# RPi-WD-Packet-Interface_-_RJ45.net
KiCad netlist of a schematic drawn in EAGLE
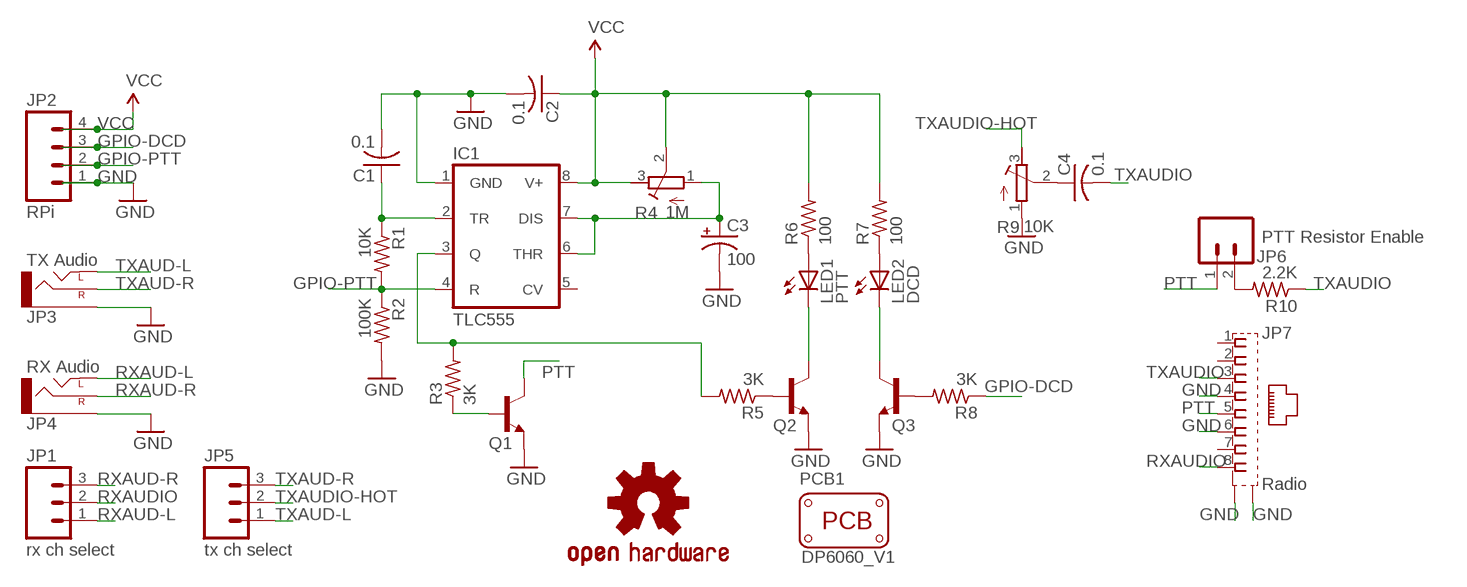
[diagram p0: schematic, sheet 1]

(export (version "E")
  (design (tool "Eeschema 10.0.6"))
  (components
    (comp (ref "C1")
      (value "0.1")
      (footprint "eagle-import:C025-025X050")
      (libsource (lib "eagle-import") (part "C-US025-025X050"))
    )
    (comp (ref "C2")
      (value "0.1")
      (footprint "eagle-import:C025-025X050")
      (libsource (lib "eagle-import") (part "C-US025-025X050"))
    )
    (comp (ref "C3")
      (value "100")
      (footprint "eagle-import:E2-5")
      (libsource (lib "eagle-import") (part "CPOL-USE2-5"))
    )
    (comp (ref "C4")
      (value "0.1")
      (footprint "eagle-import:C025-025X050")
      (libsource (lib "eagle-import") (part "C-US025-025X050"))
    )
    (comp (ref "IC1")
      (value "TLC555")
      (footprint "eagle-import:DIL08")
      (libsource (lib "eagle-import") (part "555NLM"))
    )
    (comp (ref "JP1")
      (value "rx ch select")
      (footprint "eagle-import:1X03")
      (libsource (lib "eagle-import") (part "M03PTH"))
    )
    (comp (ref "JP2")
      (value "RPi")
      (footprint "eagle-import:1X04")
      (libsource (lib "eagle-import") (part "M04PTH"))
    )
    (comp (ref "JP3")
      (value "TX Audio")
      (footprint "eagle-import:AUDIO-JACK")
      (libsource (lib "eagle-import") (part "AUDIO-JACKPTH"))
    )
    (comp (ref "JP4")
      (value "RX Audio")
      (footprint "eagle-import:AUDIO-JACK")
      (libsource (lib "eagle-import") (part "AUDIO-JACKPTH"))
    )
    (comp (ref "JP5")
      (value "tx ch select")
      (footprint "eagle-import:1X03")
      (libsource (lib "eagle-import") (part "M03PTH"))
    )
    (comp (ref "JP6")
      (value "PTT Resistor Enable")
      (footprint "eagle-import:1X02")
      (libsource (lib "eagle-import") (part "M02PTH"))
    )
    (comp (ref "JP7")
      (value "Radio")
      (footprint "eagle-import:0446200002")
      (fields (field (name "MF") "MOLEX") (field (name "MPN") "0446200002"))
      (libsource (lib "eagle-import") (part "0446200002"))
    )
    (comp (ref "LED1")
      (value "PTT")
      (footprint "eagle-import:LED5MM")
      (libsource (lib "eagle-import") (part "LED5MM"))
    )
    (comp (ref "LED2")
      (value "DCD")
      (footprint "eagle-import:LED5MM")
      (libsource (lib "eagle-import") (part "LED5MM"))
    )
    (comp (ref "LOGO1")
      (value "OSHW-LOGOM")
      (footprint "eagle-import:OSHW-LOGO-M")
      (libsource (lib "eagle-import") (part "OSHW-LOGOM"))
    )
    (comp (ref "PCB1")
      (value "PCB_DP_SQUARE-6X6")
      (footprint "eagle-import:DP6060_V1")
      (libsource (lib "eagle-import") (part "PCB_DP_SQUARE-6X6"))
    )
    (comp (ref "Q1")
      (value "PTT")
      (footprint "eagle-import:TO-92-AMMO")
      (libsource (lib "eagle-import") (part "TRANSISTOR_NPNTO-92-AMMO"))
    )
    (comp (ref "Q2")
      (value "PTT-LED")
      (footprint "eagle-import:TO-92-AMMO")
      (libsource (lib "eagle-import") (part "TRANSISTOR_NPNTO-92-AMMO"))
    )
    (comp (ref "Q3")
      (value "DCD-LED")
      (footprint "eagle-import:TO-92-AMMO")
      (libsource (lib "eagle-import") (part "TRANSISTOR_NPNTO-92-AMMO"))
    )
    (comp (ref "R1")
      (value "10K")
      (footprint "eagle-import:0207_7")
      (libsource (lib "eagle-import") (part "R-US_0207/7"))
    )
    (comp (ref "R2")
      (value "100K")
      (footprint "eagle-import:0207_7")
      (libsource (lib "eagle-import") (part "R-US_0207/7"))
    )
    (comp (ref "R3")
      (value "3K")
      (footprint "eagle-import:0207_7")
      (libsource (lib "eagle-import") (part "R-US_0207/7"))
    )
    (comp (ref "R4")
      (value "1M")
      (footprint "eagle-import:RTRIM3296W")
      (libsource (lib "eagle-import") (part "R-TRIMM3296W"))
    )
    (comp (ref "R5")
      (value "3K")
      (footprint "eagle-import:0207_7")
      (libsource (lib "eagle-import") (part "R-US_0207/7"))
    )
    (comp (ref "R6")
      (value "100")
      (footprint "eagle-import:0207_7")
      (libsource (lib "eagle-import") (part "R-US_0207/7"))
    )
    (comp (ref "R7")
      (value "100")
      (footprint "eagle-import:0207_7")
      (libsource (lib "eagle-import") (part "R-US_0207/7"))
    )
    (comp (ref "R8")
      (value "3K")
      (footprint "eagle-import:0207_7")
      (libsource (lib "eagle-import") (part "R-US_0207/7"))
    )
    (comp (ref "R9")
      (value "10K")
      (footprint "eagle-import:RTRIM3362P")
      (libsource (lib "eagle-import") (part "RTRIM-3362P"))
    )
    (comp (ref "R10")
      (value "2.2K")
      (footprint "eagle-import:0207_7")
      (libsource (lib "eagle-import") (part "R-US_0207/7"))
    )
  )
  (nets
    (net (code "1") (name "/GPIO-DCD") (class "Default")
      (node (ref "JP2") (pin "3") (pinfunction "3_3") (pintype "passive"))
      (node (ref "R8") (pin "1") (pinfunction "1_1") (pintype "passive"))
    )
    (net (code "2") (name "/GPIO-PTT") (class "Default")
      (node (ref "IC1") (pin "4") (pinfunction "R_4") (pintype "input"))
      (node (ref "JP2") (pin "2") (pinfunction "2_2") (pintype "passive"))
      (node (ref "R1") (pin "2") (pinfunction "2_2") (pintype "passive"))
      (node (ref "R2") (pin "1") (pinfunction "1_1") (pintype "passive"))
    )
    (net (code "3") (name "/PTT") (class "Default")
      (node (ref "JP6") (pin "1") (pinfunction "1_1") (pintype "passive"))
      (node (ref "JP7") (pin "5") (pinfunction "5_5") (pintype "passive"))
      (node (ref "Q1") (pin "3") (pinfunction "C_3") (pintype "passive"))
    )
    (net (code "4") (name "/RXAUD-L") (class "Default")
      (node (ref "JP1") (pin "1") (pinfunction "1_1") (pintype "passive"))
      (node (ref "JP4") (pin "TIP") (pinfunction "LEFT_TIP") (pintype "bidirectional"))
    )
    (net (code "5") (name "/RXAUD-R") (class "Default")
      (node (ref "JP1") (pin "3") (pinfunction "3_3") (pintype "passive"))
      (node (ref "JP4") (pin "RING") (pinfunction "RIGHT_RING") (pintype "bidirectional"))
    )
    (net (code "6") (name "/RXAUDIO") (class "Default")
      (node (ref "JP1") (pin "2") (pinfunction "2_2") (pintype "passive"))
      (node (ref "JP7") (pin "8") (pinfunction "8_8") (pintype "passive"))
    )
    (net (code "7") (name "/TXAUD-L") (class "Default")
      (node (ref "JP3") (pin "TIP") (pinfunction "LEFT_TIP") (pintype "bidirectional"))
      (node (ref "JP5") (pin "1") (pinfunction "1_1") (pintype "passive"))
    )
    (net (code "8") (name "/TXAUD-R") (class "Default")
      (node (ref "JP3") (pin "RING") (pinfunction "RIGHT_RING") (pintype "bidirectional"))
      (node (ref "JP5") (pin "3") (pinfunction "3_3") (pintype "passive"))
    )
    (net (code "9") (name "/TXAUDIO") (class "Default")
      (node (ref "C4") (pin "2") (pinfunction "2_2") (pintype "passive"))
      (node (ref "JP7") (pin "3") (pinfunction "3_3") (pintype "passive"))
      (node (ref "R10") (pin "1") (pinfunction "1_1") (pintype "passive"))
    )
    (net (code "10") (name "/TXAUDIO-HOT") (class "Default")
      (node (ref "JP5") (pin "2") (pinfunction "2_2") (pintype "passive"))
      (node (ref "R9") (pin "3") (pinfunction "3_3") (pintype "passive"))
    )
    (net (code "11") (name "GND") (class "Default")
      (node (ref "C1") (pin "2") (pinfunction "2_2") (pintype "passive"))
      (node (ref "C2") (pin "2") (pinfunction "2_2") (pintype "passive"))
      (node (ref "C3") (pin "-") (pinfunction "-_-") (pintype "passive"))
      (node (ref "IC1") (pin "1") (pinfunction "GND_1") (pintype "power_in"))
      (node (ref "JP2") (pin "1") (pinfunction "1_1") (pintype "passive"))
      (node (ref "JP3") (pin "SLEEVE") (pinfunction "SLEEVE_SLEEVE") (pintype "bidirectional"))
      (node (ref "JP4") (pin "SLEEVE") (pinfunction "SLEEVE_SLEEVE") (pintype "bidirectional"))
      (node (ref "JP7") (pin "4") (pinfunction "4_4") (pintype "passive"))
      (node (ref "JP7") (pin "6") (pinfunction "6_6") (pintype "passive"))
      (node (ref "JP7") (pin "S@1") (pinfunction "S1_S@1") (pintype "passive"))
      (node (ref "JP7") (pin "S@2") (pinfunction "S2_S@2") (pintype "passive"))
      (node (ref "Q1") (pin "1") (pinfunction "E_1") (pintype "passive"))
      (node (ref "Q2") (pin "1") (pinfunction "E_1") (pintype "passive"))
      (node (ref "Q3") (pin "1") (pinfunction "E_1") (pintype "passive"))
      (node (ref "R2") (pin "2") (pinfunction "2_2") (pintype "passive"))
      (node (ref "R9") (pin "1") (pinfunction "1_1") (pintype "passive"))
    )
    (net (code "12") (name "Net-(C4-Pad1)") (class "Default")
      (node (ref "C4") (pin "1") (pinfunction "1_1") (pintype "passive"))
      (node (ref "R9") (pin "2") (pinfunction "2_2") (pintype "passive"))
    )
    (net (code "13") (name "Net-(IC1-DIS)") (class "Default")
      (node (ref "C3") (pin "+") (pinfunction "+_+") (pintype "passive"))
      (node (ref "IC1") (pin "6") (pinfunction "THR_6") (pintype "input"))
      (node (ref "IC1") (pin "7") (pinfunction "DIS_7") (pintype "input"))
      (node (ref "R4") (pin "1") (pinfunction "A_1") (pintype "passive"))
    )
    (net (code "14") (name "Net-(IC1-Q)") (class "Default")
      (node (ref "IC1") (pin "3") (pinfunction "Q_3") (pintype "output"))
      (node (ref "R3") (pin "2") (pinfunction "2_2") (pintype "passive"))
      (node (ref "R5") (pin "2") (pinfunction "2_2") (pintype "passive"))
    )
    (net (code "15") (name "Net-(IC1-TR)") (class "Default")
      (node (ref "C1") (pin "1") (pinfunction "1_1") (pintype "passive"))
      (node (ref "IC1") (pin "2") (pinfunction "TR_2") (pintype "input"))
      (node (ref "R1") (pin "1") (pinfunction "1_1") (pintype "passive"))
    )
    (net (code "16") (name "Net-(JP6-Pad2)") (class "Default")
      (node (ref "JP6") (pin "2") (pinfunction "2_2") (pintype "passive"))
      (node (ref "R10") (pin "2") (pinfunction "2_2") (pintype "passive"))
    )
    (net (code "17") (name "Net-(LED1-C)") (class "Default")
      (node (ref "LED1") (pin "K") (pinfunction "C_K") (pintype "passive"))
      (node (ref "Q2") (pin "3") (pinfunction "C_3") (pintype "passive"))
    )
    (net (code "18") (name "Net-(LED1-PadA)") (class "Default")
      (node (ref "LED1") (pin "A") (pinfunction "A_A") (pintype "passive"))
      (node (ref "R6") (pin "1") (pinfunction "1_1") (pintype "passive"))
    )
    (net (code "19") (name "Net-(LED2-C)") (class "Default")
      (node (ref "LED2") (pin "K") (pinfunction "C_K") (pintype "passive"))
      (node (ref "Q3") (pin "3") (pinfunction "C_3") (pintype "passive"))
    )
    (net (code "20") (name "Net-(LED2-PadA)") (class "Default")
      (node (ref "LED2") (pin "A") (pinfunction "A_A") (pintype "passive"))
      (node (ref "R7") (pin "1") (pinfunction "1_1") (pintype "passive"))
    )
    (net (code "21") (name "Net-(Q1-B)") (class "Default")
      (node (ref "Q1") (pin "2") (pinfunction "B_2") (pintype "passive"))
      (node (ref "R3") (pin "1") (pinfunction "1_1") (pintype "passive"))
    )
    (net (code "22") (name "Net-(Q2-B)") (class "Default")
      (node (ref "Q2") (pin "2") (pinfunction "B_2") (pintype "passive"))
      (node (ref "R5") (pin "1") (pinfunction "1_1") (pintype "passive"))
    )
    (net (code "23") (name "Net-(Q3-B)") (class "Default")
      (node (ref "Q3") (pin "2") (pinfunction "B_2") (pintype "passive"))
      (node (ref "R8") (pin "2") (pinfunction "2_2") (pintype "passive"))
    )
    (net (code "24") (name "VCC") (class "Default")
      (node (ref "C2") (pin "1") (pinfunction "1_1") (pintype "passive"))
      (node (ref "IC1") (pin "8") (pinfunction "V+_8") (pintype "power_in"))
      (node (ref "JP2") (pin "4") (pinfunction "4_4") (pintype "passive"))
      (node (ref "R4") (pin "2") (pinfunction "S_2") (pintype "passive"))
      (node (ref "R4") (pin "3") (pinfunction "E_3") (pintype "passive"))
      (node (ref "R6") (pin "2") (pinfunction "2_2") (pintype "passive"))
      (node (ref "R7") (pin "2") (pinfunction "2_2") (pintype "passive"))
    )
    (net (code "25") (name "unconnected-(IC1-CV-Pad5)") (class "Default")
      (node (ref "IC1") (pin "5") (pinfunction "CV_5") (pintype "input"))
    )
    (net (code "26") (name "unconnected-(JP7-Pad1)") (class "Default")
      (node (ref "JP7") (pin "1") (pinfunction "1_1") (pintype "passive"))
    )
    (net (code "27") (name "unconnected-(JP7-Pad2)") (class "Default")
      (node (ref "JP7") (pin "2") (pinfunction "2_2") (pintype "passive"))
    )
    (net (code "28") (name "unconnected-(JP7-Pad7)") (class "Default")
      (node (ref "JP7") (pin "7") (pinfunction "7_7") (pintype "passive"))
    )
  )
)
